# javi_VCAvolumenContol_revB.net
KiCad netlist of a schematic drawn in EAGLE
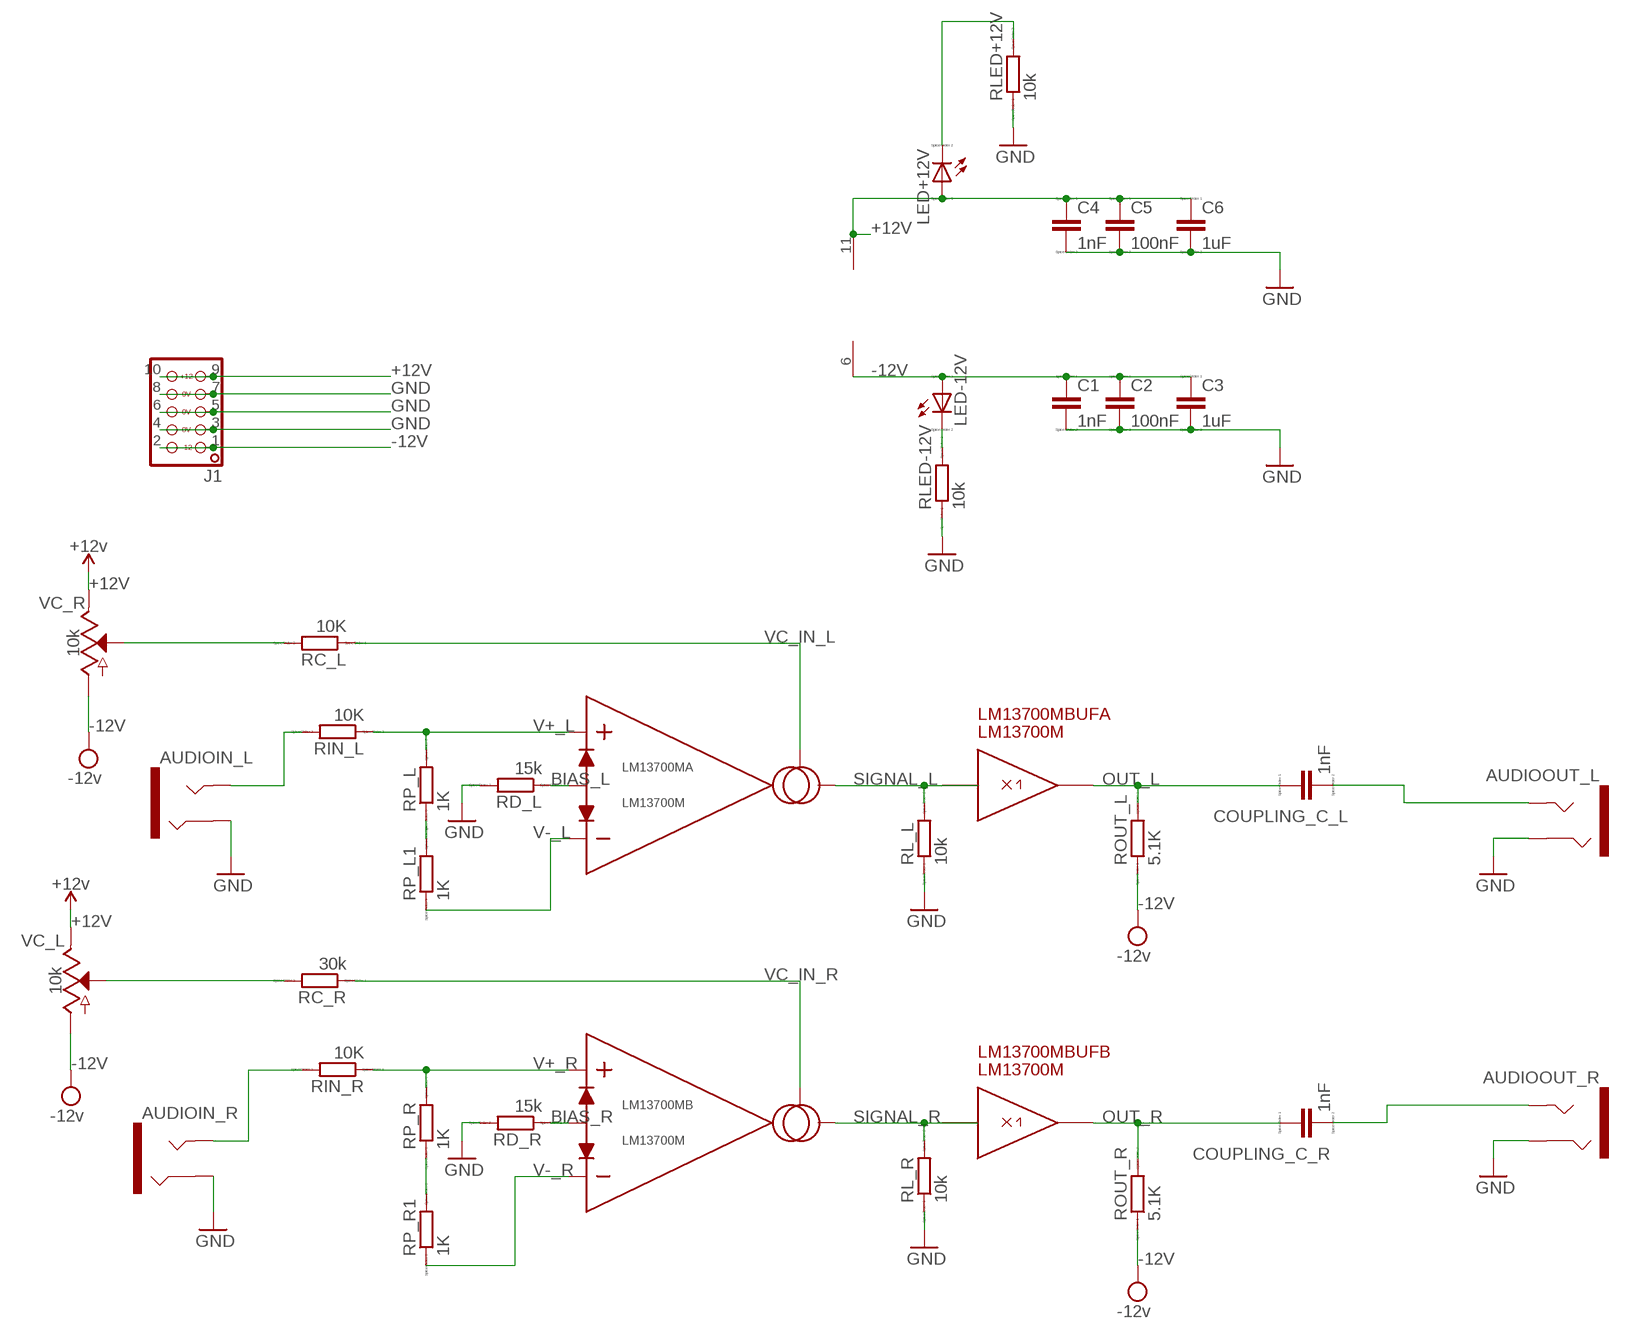
[diagram p0: schematic, sheet 1]

(export (version "E")
  (design (tool "Eeschema 10.0.6"))
  (components
    (comp (ref "AUDIOIN_L")
      (value "AUDIO_JACK_TRS_0.25\"_PTH_VERTICAL")
      (footprint "eagle-import:AUDIO_JACK_0.25__TRS_PTH_VERTICAL")
      (libsource (lib "eagle-import") (part "AUDIO_JACK_TRS_0.25{dblquote}_PTH_VERTICAL"))
    )
    (comp (ref "AUDIOIN_R")
      (value "AUDIO_JACK_TRS_0.25\"_PTH_VERTICAL")
      (footprint "eagle-import:AUDIO_JACK_0.25__TRS_PTH_VERTICAL")
      (libsource (lib "eagle-import") (part "AUDIO_JACK_TRS_0.25{dblquote}_PTH_VERTICAL"))
    )
    (comp (ref "AUDIOOUT_L")
      (value "AUDIO_JACK_TRS_0.25\"_PTH_VERTICAL")
      (footprint "eagle-import:AUDIO_JACK_0.25__TRS_PTH_VERTICAL")
      (libsource (lib "eagle-import") (part "AUDIO_JACK_TRS_0.25{dblquote}_PTH_VERTICAL"))
    )
    (comp (ref "AUDIOOUT_R")
      (value "AUDIO_JACK_TRS_0.25\"_PTH_VERTICAL")
      (footprint "eagle-import:AUDIO_JACK_0.25__TRS_PTH_VERTICAL")
      (libsource (lib "eagle-import") (part "AUDIO_JACK_TRS_0.25{dblquote}_PTH_VERTICAL"))
    )
    (comp (ref "C1")
      (value "1nF")
      (footprint "eagle-import:C0805")
      (libsource (lib "eagle-import") (part "C"))
    )
    (comp (ref "C2")
      (value "100nF")
      (footprint "eagle-import:C0805")
      (libsource (lib "eagle-import") (part "C"))
    )
    (comp (ref "C3")
      (value "1uF")
      (footprint "eagle-import:C0805")
      (libsource (lib "eagle-import") (part "C"))
    )
    (comp (ref "C4")
      (value "1nF")
      (footprint "eagle-import:C0805")
      (libsource (lib "eagle-import") (part "C"))
    )
    (comp (ref "C5")
      (value "100nF")
      (footprint "eagle-import:C0805")
      (libsource (lib "eagle-import") (part "C"))
    )
    (comp (ref "C6")
      (value "1uF")
      (footprint "eagle-import:C0805")
      (libsource (lib "eagle-import") (part "C"))
    )
    (comp (ref "COUPLING_C_L")
      (value "1nF")
      (footprint "eagle-import:C0805")
      (libsource (lib "eagle-import") (part "C"))
    )
    (comp (ref "COUPLING_C_R")
      (value "1nF")
      (footprint "eagle-import:C0805")
      (libsource (lib "eagle-import") (part "C"))
    )
    (comp (ref "J1")
      (value "EUROPWR_2X05-SMD")
      (footprint "eagle-import:2X05_EUROPWR_SMD")
      (libsource (lib "eagle-import") (part "EUROPWR_2X05-SMD"))
    )
    (comp (ref "LED+12V")
      (value "LED_E")
      (footprint "eagle-import:LED_1206")
      (libsource (lib "eagle-import") (part "LED_E"))
    )
    (comp (ref "LED-12V")
      (value "LED_E")
      (footprint "eagle-import:LED_1206")
      (libsource (lib "eagle-import") (part "LED_E"))
    )
    (comp (ref "LM13700M")
      (value "LM13700M")
      (footprint "eagle-import:SO16")
      (libsource (lib "eagle-import") (part "LM13700M"))
    )
    (comp (ref "RC_L")
      (value "10K")
      (footprint "eagle-import:R0805")
      (libsource (lib "eagle-import") (part "R"))
    )
    (comp (ref "RC_R")
      (value "30k")
      (footprint "eagle-import:R0805")
      (libsource (lib "eagle-import") (part "R"))
    )
    (comp (ref "RD_L")
      (value "15k")
      (footprint "eagle-import:R0805")
      (libsource (lib "eagle-import") (part "R"))
    )
    (comp (ref "RD_R")
      (value "15k")
      (footprint "eagle-import:R0805")
      (libsource (lib "eagle-import") (part "R"))
    )
    (comp (ref "RIN_L")
      (value "10K")
      (footprint "eagle-import:R0805")
      (libsource (lib "eagle-import") (part "R"))
    )
    (comp (ref "RIN_R")
      (value "10K")
      (footprint "eagle-import:R0805")
      (libsource (lib "eagle-import") (part "R"))
    )
    (comp (ref "RLED+12V")
      (value "10k")
      (footprint "eagle-import:R0805")
      (libsource (lib "eagle-import") (part "R"))
    )
    (comp (ref "RLED-12V")
      (value "10k")
      (footprint "eagle-import:R0805")
      (libsource (lib "eagle-import") (part "R"))
    )
    (comp (ref "RL_L")
      (value "10k")
      (footprint "eagle-import:R0805")
      (libsource (lib "eagle-import") (part "R"))
    )
    (comp (ref "RL_R")
      (value "10k")
      (footprint "eagle-import:R0805")
      (libsource (lib "eagle-import") (part "R"))
    )
    (comp (ref "ROUT_L")
      (value "5.1K")
      (footprint "eagle-import:R0805")
      (libsource (lib "eagle-import") (part "R"))
    )
    (comp (ref "ROUT_R")
      (value "5.1K")
      (footprint "eagle-import:R0805")
      (libsource (lib "eagle-import") (part "R"))
    )
    (comp (ref "RP_L")
      (value "1K")
      (footprint "eagle-import:R0805")
      (libsource (lib "eagle-import") (part "R"))
    )
    (comp (ref "RP_L1")
      (value "1K")
      (footprint "eagle-import:R0805")
      (libsource (lib "eagle-import") (part "R"))
    )
    (comp (ref "RP_R")
      (value "1K")
      (footprint "eagle-import:R0805")
      (libsource (lib "eagle-import") (part "R"))
    )
    (comp (ref "RP_R1")
      (value "1K")
      (footprint "eagle-import:R0805")
      (libsource (lib "eagle-import") (part "R"))
    )
    (comp (ref "VC_L")
      (value "10k")
      (footprint "eagle-import:POT-PTH-ALPS")
      (libsource (lib "eagle-import") (part "POTENTIOMETER-PTH-9MM-1/20W-20%"))
    )
    (comp (ref "VC_R")
      (value "10k")
      (footprint "eagle-import:POT-PTH-ALPS")
      (libsource (lib "eagle-import") (part "POTENTIOMETER-PTH-9MM-1/20W-20%"))
    )
  )
  (nets
    (net (code "1") (name "+12v") (class "Default")
      (node (ref "C4") (pin "1") (pinfunction "1_1") (pintype "passive"))
      (node (ref "C5") (pin "1") (pinfunction "1_1") (pintype "passive"))
      (node (ref "C6") (pin "1") (pinfunction "1_1") (pintype "passive"))
      (node (ref "J1") (pin "10") (pinfunction "10_10") (pintype "passive"))
      (node (ref "J1") (pin "9") (pinfunction "9_9") (pintype "passive"))
      (node (ref "LED+12V") (pin "A") (pinfunction "A_A") (pintype "passive"))
      (node (ref "LM13700M") (pin "11") (pinfunction "VEE_11") (pintype "power_in"))
      (node (ref "VC_L") (pin "P$1") (pinfunction "E_P$1") (pintype "passive"))
      (node (ref "VC_R") (pin "P$1") (pinfunction "E_P$1") (pintype "passive"))
    )
    (net (code "2") (name "-12v") (class "Default")
      (node (ref "C1") (pin "1") (pinfunction "1_1") (pintype "passive"))
      (node (ref "C2") (pin "1") (pinfunction "1_1") (pintype "passive"))
      (node (ref "C3") (pin "1") (pinfunction "1_1") (pintype "passive"))
      (node (ref "J1") (pin "1") (pinfunction "1_1") (pintype "passive"))
      (node (ref "J1") (pin "2") (pinfunction "2_2") (pintype "passive"))
      (node (ref "LED-12V") (pin "A") (pinfunction "A_A") (pintype "passive"))
      (node (ref "LM13700M") (pin "6") (pinfunction "VCC_6") (pintype "power_in"))
      (node (ref "ROUT_L") (pin "1") (pinfunction "1_1") (pintype "passive"))
      (node (ref "ROUT_R") (pin "1") (pinfunction "1_1") (pintype "passive"))
      (node (ref "VC_L") (pin "P$3") (pinfunction "A_P$3") (pintype "passive"))
      (node (ref "VC_R") (pin "P$3") (pinfunction "A_P$3") (pintype "passive"))
    )
    (net (code "3") (name "/BIAS_L") (class "Default")
      (node (ref "LM13700M") (pin "2") (pinfunction "BIAS_2") (pintype "input"))
      (node (ref "RD_L") (pin "1") (pinfunction "1_1") (pintype "passive"))
    )
    (net (code "4") (name "/BIAS_R") (class "Default")
      (node (ref "LM13700M") (pin "15") (pinfunction "BIAS_15") (pintype "input"))
      (node (ref "RD_R") (pin "1") (pinfunction "1_1") (pintype "passive"))
    )
    (net (code "5") (name "/OUT_L") (class "Default")
      (node (ref "COUPLING_C_L") (pin "1") (pinfunction "1_1") (pintype "passive"))
      (node (ref "LM13700M") (pin "8") (pinfunction "OUT_8") (pintype "bidirectional"))
      (node (ref "ROUT_L") (pin "2") (pinfunction "2_2") (pintype "passive"))
    )
    (net (code "6") (name "/OUT_R") (class "Default")
      (node (ref "COUPLING_C_R") (pin "1") (pinfunction "1_1") (pintype "passive"))
      (node (ref "LM13700M") (pin "9") (pinfunction "OUT_9") (pintype "bidirectional"))
      (node (ref "ROUT_R") (pin "2") (pinfunction "2_2") (pintype "passive"))
    )
    (net (code "7") (name "/SIGNAL_L") (class "Default")
      (node (ref "LM13700M") (pin "5") (pinfunction "IOUT_5") (pintype "output"))
      (node (ref "LM13700M") (pin "7") (pinfunction "IN_7") (pintype "bidirectional"))
      (node (ref "RL_L") (pin "2") (pinfunction "2_2") (pintype "passive"))
    )
    (net (code "8") (name "/SIGNAL_R") (class "Default")
      (node (ref "LM13700M") (pin "10") (pinfunction "IN_10") (pintype "bidirectional"))
      (node (ref "LM13700M") (pin "12") (pinfunction "IOUT_12") (pintype "output"))
      (node (ref "RL_R") (pin "2") (pinfunction "2_2") (pintype "passive"))
    )
    (net (code "9") (name "/V+_L") (class "Default")
      (node (ref "LM13700M") (pin "3") (pinfunction "IN+_3") (pintype "input"))
      (node (ref "RIN_L") (pin "1") (pinfunction "1_1") (pintype "passive"))
      (node (ref "RP_L") (pin "2") (pinfunction "2_2") (pintype "passive"))
    )
    (net (code "10") (name "/V+_R") (class "Default")
      (node (ref "LM13700M") (pin "14") (pinfunction "IN+_14") (pintype "input"))
      (node (ref "RIN_R") (pin "1") (pinfunction "1_1") (pintype "passive"))
      (node (ref "RP_R") (pin "2") (pinfunction "2_2") (pintype "passive"))
    )
    (net (code "11") (name "/V-_L") (class "Default")
      (node (ref "LM13700M") (pin "4") (pinfunction "IN-_4") (pintype "input"))
      (node (ref "RP_L1") (pin "1") (pinfunction "1_1") (pintype "passive"))
    )
    (net (code "12") (name "/V-_R") (class "Default")
      (node (ref "LM13700M") (pin "13") (pinfunction "IN-_13") (pintype "input"))
      (node (ref "RP_R1") (pin "1") (pinfunction "1_1") (pintype "passive"))
    )
    (net (code "13") (name "/VC_IN_L") (class "Default")
      (node (ref "LM13700M") (pin "1") (pinfunction "IABC_1") (pintype "input"))
      (node (ref "RC_L") (pin "1") (pinfunction "1_1") (pintype "passive"))
    )
    (net (code "14") (name "/VC_IN_R") (class "Default")
      (node (ref "LM13700M") (pin "16") (pinfunction "IABC_16") (pintype "input"))
      (node (ref "RC_R") (pin "1") (pinfunction "1_1") (pintype "passive"))
    )
    (net (code "15") (name "GND") (class "Default")
      (node (ref "AUDIOIN_L") (pin "RING") (pinfunction "RING_RING") (pintype "bidirectional"))
      (node (ref "AUDIOIN_R") (pin "RING") (pinfunction "RING_RING") (pintype "bidirectional"))
      (node (ref "AUDIOOUT_L") (pin "RING") (pinfunction "RING_RING") (pintype "bidirectional"))
      (node (ref "AUDIOOUT_R") (pin "RING") (pinfunction "RING_RING") (pintype "bidirectional"))
      (node (ref "C1") (pin "2") (pinfunction "2_2") (pintype "passive"))
      (node (ref "C2") (pin "2") (pinfunction "2_2") (pintype "passive"))
      (node (ref "C3") (pin "2") (pinfunction "2_2") (pintype "passive"))
      (node (ref "C4") (pin "2") (pinfunction "2_2") (pintype "passive"))
      (node (ref "C5") (pin "2") (pinfunction "2_2") (pintype "passive"))
      (node (ref "C6") (pin "2") (pinfunction "2_2") (pintype "passive"))
      (node (ref "J1") (pin "3") (pinfunction "3_3") (pintype "passive"))
      (node (ref "J1") (pin "4") (pinfunction "4_4") (pintype "passive"))
      (node (ref "J1") (pin "5") (pinfunction "5_5") (pintype "passive"))
      (node (ref "J1") (pin "6") (pinfunction "6_6") (pintype "passive"))
      (node (ref "J1") (pin "7") (pinfunction "7_7") (pintype "passive"))
      (node (ref "J1") (pin "8") (pinfunction "8_8") (pintype "passive"))
      (node (ref "RD_L") (pin "2") (pinfunction "2_2") (pintype "passive"))
      (node (ref "RD_R") (pin "2") (pinfunction "2_2") (pintype "passive"))
      (node (ref "RLED+12V") (pin "1") (pinfunction "1_1") (pintype "passive"))
      (node (ref "RLED-12V") (pin "1") (pinfunction "1_1") (pintype "passive"))
      (node (ref "RL_L") (pin "1") (pinfunction "1_1") (pintype "passive"))
      (node (ref "RL_R") (pin "1") (pinfunction "1_1") (pintype "passive"))
    )
    (net (code "16") (name "Net-(AUDIOIN_L-PadTIP)") (class "Default")
      (node (ref "AUDIOIN_L") (pin "TIP") (pinfunction "TIP_TIP") (pintype "bidirectional"))
      (node (ref "RIN_L") (pin "2") (pinfunction "2_2") (pintype "passive"))
    )
    (net (code "17") (name "Net-(AUDIOIN_R-PadTIP)") (class "Default")
      (node (ref "AUDIOIN_R") (pin "TIP") (pinfunction "TIP_TIP") (pintype "bidirectional"))
      (node (ref "RIN_R") (pin "2") (pinfunction "2_2") (pintype "passive"))
    )
    (net (code "18") (name "Net-(AUDIOOUT_L-PadTIP)") (class "Default")
      (node (ref "AUDIOOUT_L") (pin "TIP") (pinfunction "TIP_TIP") (pintype "bidirectional"))
      (node (ref "COUPLING_C_L") (pin "2") (pinfunction "2_2") (pintype "passive"))
    )
    (net (code "19") (name "Net-(AUDIOOUT_R-PadTIP)") (class "Default")
      (node (ref "AUDIOOUT_R") (pin "TIP") (pinfunction "TIP_TIP") (pintype "bidirectional"))
      (node (ref "COUPLING_C_R") (pin "2") (pinfunction "2_2") (pintype "passive"))
    )
    (net (code "20") (name "Net-(LED+12V-PadC)") (class "Default")
      (node (ref "LED+12V") (pin "C") (pinfunction "C_C") (pintype "passive"))
      (node (ref "RLED+12V") (pin "2") (pinfunction "2_2") (pintype "passive"))
    )
    (net (code "21") (name "Net-(LED-12V-PadC)") (class "Default")
      (node (ref "LED-12V") (pin "C") (pinfunction "C_C") (pintype "passive"))
      (node (ref "RLED-12V") (pin "2") (pinfunction "2_2") (pintype "passive"))
    )
    (net (code "22") (name "Net-(RP_L-Pad1)") (class "Default")
      (node (ref "RP_L") (pin "1") (pinfunction "1_1") (pintype "passive"))
      (node (ref "RP_L1") (pin "2") (pinfunction "2_2") (pintype "passive"))
    )
    (net (code "23") (name "Net-(RP_R-Pad1)") (class "Default")
      (node (ref "RP_R") (pin "1") (pinfunction "1_1") (pintype "passive"))
      (node (ref "RP_R1") (pin "2") (pinfunction "2_2") (pintype "passive"))
    )
    (net (code "24") (name "Net-(VC_L-S)") (class "Default")
      (node (ref "RC_R") (pin "2") (pinfunction "2_2") (pintype "passive"))
      (node (ref "VC_L") (pin "P$2") (pinfunction "S_P$2") (pintype "passive"))
    )
    (net (code "25") (name "Net-(VC_R-S)") (class "Default")
      (node (ref "RC_L") (pin "2") (pinfunction "2_2") (pintype "passive"))
      (node (ref "VC_R") (pin "P$2") (pinfunction "S_P$2") (pintype "passive"))
    )
  )
)
